# GPS_adapter.net
KiCad netlist of a schematic drawn in EAGLE
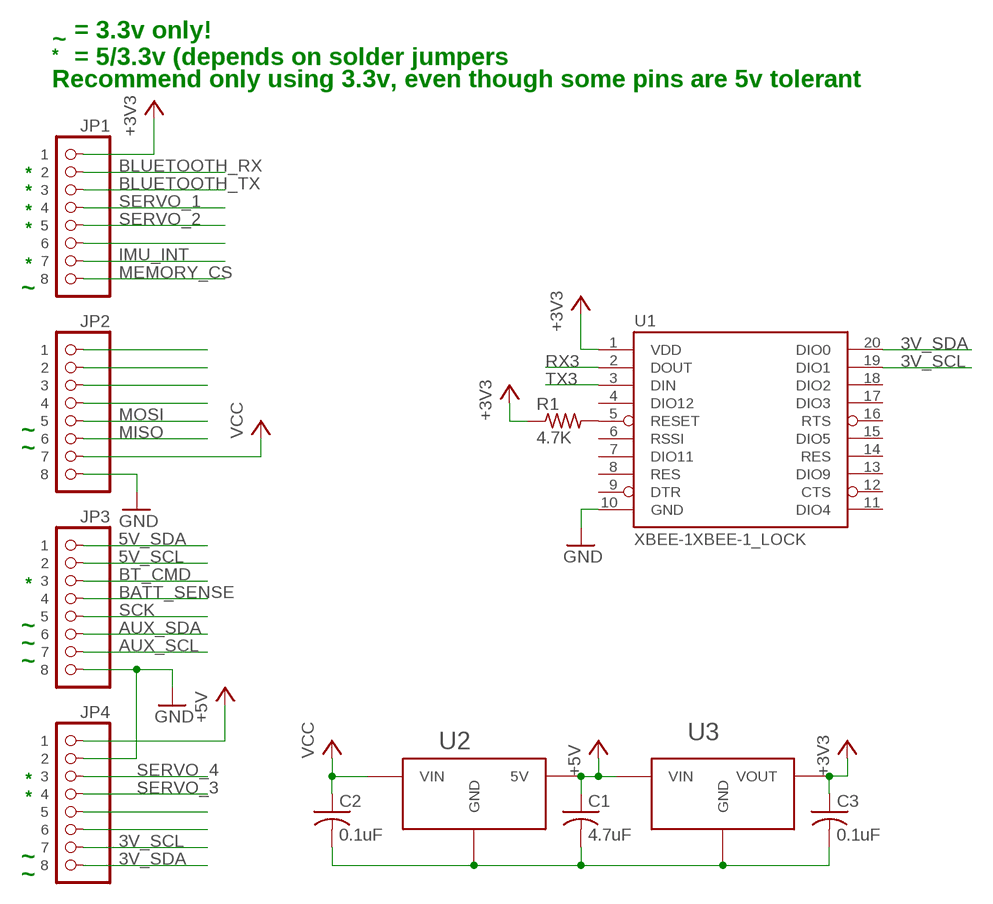
[diagram p0: schematic, sheet 1]

(export (version "E")
  (design (tool "Eeschema 10.0.6"))
  (components
    (comp (ref "C1")
      (value "4.7uF")
      (footprint "eagle-import:C0603")
      (libsource (lib "eagle-import") (part "C-USC0603"))
    )
    (comp (ref "C2")
      (value "0.1uF")
      (footprint "eagle-import:C0603")
      (libsource (lib "eagle-import") (part "C-USC0603"))
    )
    (comp (ref "C3")
      (value "0.1uF")
      (footprint "eagle-import:C0603")
      (libsource (lib "eagle-import") (part "C-USC0603"))
    )
    (comp (ref "JP1")
      (value "8-PIN_HEADER")
      (footprint "eagle-import:8-PIN_RECEPTACLE_LOCK_NO-SS")
      (libsource (lib "eagle-import") (part "8-PIN_HEADER"))
    )
    (comp (ref "JP2")
      (value "8-PIN_HEADER")
      (footprint "eagle-import:8-PIN_RECEPTACLE_LOCK_NO-SS")
      (libsource (lib "eagle-import") (part "8-PIN_HEADER"))
    )
    (comp (ref "JP3")
      (value "8-PIN_HEADER")
      (footprint "eagle-import:8-PIN_RECEPTACLE_LOCK_NO-SS")
      (libsource (lib "eagle-import") (part "8-PIN_HEADER"))
    )
    (comp (ref "JP4")
      (value "8-PIN_HEADER")
      (footprint "eagle-import:8-PIN_RECEPTACLE_LOCK_NO-SS")
      (libsource (lib "eagle-import") (part "8-PIN_HEADER"))
    )
    (comp (ref "R1")
      (value "4.7K")
      (footprint "eagle-import:R0603")
      (libsource (lib "eagle-import") (part "R-US_R0603"))
    )
    (comp (ref "U1")
      (value "XBEE-1XBEE-1_LOCK")
      (footprint "eagle-import:XBEE-1_LOCK")
      (libsource (lib "eagle-import") (part "XBEE-1XBEE-1_LOCK"))
    )
    (comp (ref "U2")
      (value "LM2931")
      (footprint "eagle-import:TO263")
      (libsource (lib "eagle-import") (part "LM2931"))
    )
    (comp (ref "U3")
      (value "AP7313SOT23R")
      (footprint "eagle-import:SOT23")
      (libsource (lib "eagle-import") (part "AP7313SOT23R"))
    )
  )
  (nets
    (net (code "1") (name "+3V3") (class "Default")
      (node (ref "C3") (pin "1") (pinfunction "1_1") (pintype "passive"))
      (node (ref "JP1") (pin "P$1") (pinfunction "1_P$1") (pintype "passive"))
      (node (ref "R1") (pin "1") (pinfunction "1_1") (pintype "passive"))
      (node (ref "U1") (pin "1") (pinfunction "VDD_1") (pintype "power_in"))
      (node (ref "U3") (pin "P$2") (pinfunction "VOUT_P$2") (pintype "bidirectional"))
    )
    (net (code "2") (name "+5V") (class "Default")
      (node (ref "C1") (pin "1") (pinfunction "1_1") (pintype "passive"))
      (node (ref "JP4") (pin "P$1") (pinfunction "1_P$1") (pintype "passive"))
      (node (ref "U2") (pin "P$3") (pinfunction "5V_P$3") (pintype "bidirectional"))
      (node (ref "U3") (pin "P$3") (pinfunction "VIN_P$3") (pintype "bidirectional"))
    )
    (net (code "3") (name "/3V_SCL") (class "Default")
      (node (ref "JP4") (pin "P$7") (pinfunction "7_P$7") (pintype "passive"))
      (node (ref "U1") (pin "19") (pinfunction "DIO1_19") (pintype "bidirectional"))
    )
    (net (code "4") (name "/3V_SDA") (class "Default")
      (node (ref "JP4") (pin "P$8") (pinfunction "8_P$8") (pintype "passive"))
      (node (ref "U1") (pin "20") (pinfunction "DIO0_20") (pintype "bidirectional"))
    )
    (net (code "5") (name "/5V_SCL") (class "Default")
      (node (ref "JP3") (pin "P$2") (pinfunction "2_P$2") (pintype "passive"))
    )
    (net (code "6") (name "/5V_SDA") (class "Default")
      (node (ref "JP3") (pin "P$1") (pinfunction "1_P$1") (pintype "passive"))
    )
    (net (code "7") (name "/AUX_SCL") (class "Default")
      (node (ref "JP3") (pin "P$7") (pinfunction "7_P$7") (pintype "passive"))
    )
    (net (code "8") (name "/AUX_SDA") (class "Default")
      (node (ref "JP3") (pin "P$6") (pinfunction "6_P$6") (pintype "passive"))
    )
    (net (code "9") (name "/BATT_SENSE") (class "Default")
      (node (ref "JP3") (pin "P$4") (pinfunction "4_P$4") (pintype "passive"))
    )
    (net (code "10") (name "/BLUETOOTH_RX") (class "Default")
      (node (ref "JP1") (pin "P$2") (pinfunction "2_P$2") (pintype "passive"))
    )
    (net (code "11") (name "/BLUETOOTH_TX") (class "Default")
      (node (ref "JP1") (pin "P$3") (pinfunction "3_P$3") (pintype "passive"))
    )
    (net (code "12") (name "/BT_CMD") (class "Default")
      (node (ref "JP3") (pin "P$3") (pinfunction "3_P$3") (pintype "passive"))
    )
    (net (code "13") (name "/IMU_INT") (class "Default")
      (node (ref "JP1") (pin "P$7") (pinfunction "7_P$7") (pintype "passive"))
    )
    (net (code "14") (name "/MEMORY_CS") (class "Default")
      (node (ref "JP1") (pin "P$8") (pinfunction "8_P$8") (pintype "passive"))
    )
    (net (code "15") (name "/MISO") (class "Default")
      (node (ref "JP2") (pin "P$6") (pinfunction "6_P$6") (pintype "passive"))
    )
    (net (code "16") (name "/MOSI") (class "Default")
      (node (ref "JP2") (pin "P$5") (pinfunction "5_P$5") (pintype "passive"))
    )
    (net (code "17") (name "/RX3") (class "Default")
      (node (ref "U1") (pin "2") (pinfunction "DOUT_2") (pintype "output"))
    )
    (net (code "18") (name "/SCK") (class "Default")
      (node (ref "JP3") (pin "P$5") (pinfunction "5_P$5") (pintype "passive"))
    )
    (net (code "19") (name "/SERVO_1") (class "Default")
      (node (ref "JP1") (pin "P$4") (pinfunction "4_P$4") (pintype "passive"))
    )
    (net (code "20") (name "/SERVO_2") (class "Default")
      (node (ref "JP1") (pin "P$5") (pinfunction "5_P$5") (pintype "passive"))
    )
    (net (code "21") (name "/SERVO_3") (class "Default")
      (node (ref "JP4") (pin "P$4") (pinfunction "4_P$4") (pintype "passive"))
    )
    (net (code "22") (name "/SERVO_4") (class "Default")
      (node (ref "JP4") (pin "P$3") (pinfunction "3_P$3") (pintype "passive"))
    )
    (net (code "23") (name "/TX3") (class "Default")
      (node (ref "U1") (pin "3") (pinfunction "DIN_3") (pintype "input"))
    )
    (net (code "24") (name "GND") (class "Default")
      (node (ref "JP2") (pin "P$8") (pinfunction "8_P$8") (pintype "passive"))
      (node (ref "JP3") (pin "P$8") (pinfunction "8_P$8") (pintype "passive"))
      (node (ref "JP4") (pin "P$2") (pinfunction "2_P$2") (pintype "passive"))
      (node (ref "U1") (pin "10") (pinfunction "GND_10") (pintype "power_in"))
    )
    (net (code "25") (name "Net-(U1-RESET)") (class "Default")
      (node (ref "R1") (pin "2") (pinfunction "2_2") (pintype "passive"))
      (node (ref "U1") (pin "5") (pinfunction "RESET_5") (pintype "input"))
    )
    (net (code "26") (name "Net-(U2-GND)") (class "Default")
      (node (ref "C1") (pin "2") (pinfunction "2_2") (pintype "passive"))
      (node (ref "C2") (pin "2") (pinfunction "2_2") (pintype "passive"))
      (node (ref "C3") (pin "2") (pinfunction "2_2") (pintype "passive"))
      (node (ref "U2") (pin "P$1") (pinfunction "GND_P$1") (pintype "bidirectional"))
      (node (ref "U3") (pin "P$1") (pinfunction "GND_P$1") (pintype "bidirectional"))
    )
    (net (code "27") (name "VCC") (class "Default")
      (node (ref "C2") (pin "1") (pinfunction "1_1") (pintype "passive"))
      (node (ref "JP2") (pin "P$7") (pinfunction "7_P$7") (pintype "passive"))
      (node (ref "U2") (pin "P$2") (pinfunction "VIN_P$2") (pintype "bidirectional"))
    )
    (net (code "28") (name "unconnected-(JP1-6-PadP$6)") (class "Default")
      (node (ref "JP1") (pin "P$6") (pinfunction "6_P$6") (pintype "passive"))
    )
    (net (code "29") (name "unconnected-(JP2-1-PadP$1)") (class "Default")
      (node (ref "JP2") (pin "P$1") (pinfunction "1_P$1") (pintype "passive"))
    )
    (net (code "30") (name "unconnected-(JP2-2-PadP$2)") (class "Default")
      (node (ref "JP2") (pin "P$2") (pinfunction "2_P$2") (pintype "passive"))
    )
    (net (code "31") (name "unconnected-(JP2-3-PadP$3)") (class "Default")
      (node (ref "JP2") (pin "P$3") (pinfunction "3_P$3") (pintype "passive"))
    )
    (net (code "32") (name "unconnected-(JP2-4-PadP$4)") (class "Default")
      (node (ref "JP2") (pin "P$4") (pinfunction "4_P$4") (pintype "passive"))
    )
    (net (code "33") (name "unconnected-(JP4-5-PadP$5)") (class "Default")
      (node (ref "JP4") (pin "P$5") (pinfunction "5_P$5") (pintype "passive"))
    )
    (net (code "34") (name "unconnected-(JP4-6-PadP$6)") (class "Default")
      (node (ref "JP4") (pin "P$6") (pinfunction "6_P$6") (pintype "passive"))
    )
    (net (code "35") (name "unconnected-(U1-CTS-Pad12)") (class "Default")
      (node (ref "U1") (pin "12") (pinfunction "CTS_12") (pintype "output"))
    )
    (net (code "36") (name "unconnected-(U1-DIO2-Pad18)") (class "Default")
      (node (ref "U1") (pin "18") (pinfunction "DIO2_18") (pintype "bidirectional"))
    )
    (net (code "37") (name "unconnected-(U1-DIO3-Pad17)") (class "Default")
      (node (ref "U1") (pin "17") (pinfunction "DIO3_17") (pintype "bidirectional"))
    )
    (net (code "38") (name "unconnected-(U1-DIO4-Pad11)") (class "Default")
      (node (ref "U1") (pin "11") (pinfunction "DIO4_11") (pintype "bidirectional"))
    )
    (net (code "39") (name "unconnected-(U1-DIO5-Pad15)") (class "Default")
      (node (ref "U1") (pin "15") (pinfunction "DIO5_15") (pintype "bidirectional"))
    )
    (net (code "40") (name "unconnected-(U1-DIO9-Pad13)") (class "Default")
      (node (ref "U1") (pin "13") (pinfunction "DIO9_13") (pintype "bidirectional"))
    )
    (net (code "41") (name "unconnected-(U1-DIO11-Pad7)") (class "Default")
      (node (ref "U1") (pin "7") (pinfunction "DIO11_7") (pintype "bidirectional"))
    )
    (net (code "42") (name "unconnected-(U1-DIO12-Pad4)") (class "Default")
      (node (ref "U1") (pin "4") (pinfunction "DIO12_4") (pintype "bidirectional"))
    )
    (net (code "43") (name "unconnected-(U1-DTR-Pad9)") (class "Default")
      (node (ref "U1") (pin "9") (pinfunction "DTR_9") (pintype "bidirectional"))
    )
    (net (code "44") (name "unconnected-(U1-RES-Pad8)") (class "Default")
      (node (ref "U1") (pin "8") (pinfunction "RES_8") (pintype "bidirectional"))
    )
    (net (code "45") (name "unconnected-(U1-RES-Pad14)") (class "Default")
      (node (ref "U1") (pin "14") (pinfunction "RES_14") (pintype "bidirectional"))
    )
    (net (code "46") (name "unconnected-(U1-RSSI-Pad6)") (class "Default")
      (node (ref "U1") (pin "6") (pinfunction "RSSI_6") (pintype "bidirectional"))
    )
    (net (code "47") (name "unconnected-(U1-RTS-Pad16)") (class "Default")
      (node (ref "U1") (pin "16") (pinfunction "RTS_16") (pintype "input"))
    )
  )
)
